# JFET.net
KiCad netlist of a schematic drawn in Altium Designer
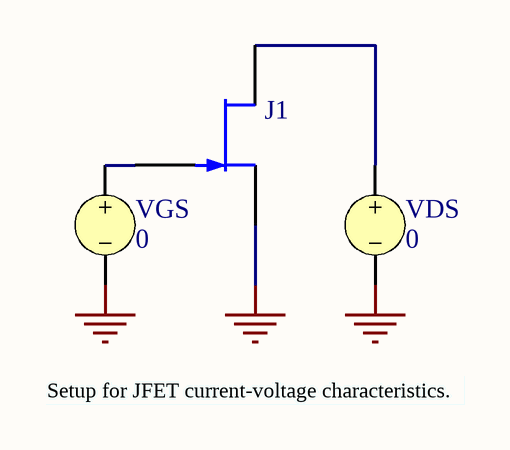
[diagram p0: JFET.SchDoc]

(export (version "E")
  (design (tool "Eeschema 10.0.6"))
  (components
    (comp (ref "J1")
      (value "NE38018-T1")
      (footprint "SOT343/P1.3")
      (description "N-channel junction fet")
      (libsource (lib "NE38018") (part "NE38018-T1"))
    )
    (comp (ref "VDS")
      (value "0")
      (description "Voltage Source")
      (fields (field (name "MANUFACTURER") "Generic Components") (field (name "Comment") "VSRC"))
      (libsource (lib "Simulation Sources") (part "VSRC"))
    )
    (comp (ref "VGS")
      (value "0")
      (description "Voltage Source")
      (fields (field (name "MANUFACTURER") "Generic Components") (field (name "Comment") "VSRC"))
      (libsource (lib "Simulation Sources") (part "VSRC"))
    )
  )
  (nets
    (net (code "1") (name "GND") (class "Default")
      (node (ref "J1") (pin "1") (pinfunction "S_1") (pintype "passive"))
      (node (ref "VDS") (pin "2") (pinfunction "2_2") (pintype "passive"))
      (node (ref "VGS") (pin "2") (pinfunction "2_2") (pintype "passive"))
    )
    (net (code "2") (name "Net-(J1-D)") (class "Default")
      (node (ref "J1") (pin "4") (pinfunction "D_4") (pintype "passive"))
      (node (ref "VDS") (pin "1") (pinfunction "1_1") (pintype "passive"))
    )
    (net (code "3") (name "Net-(J1-G)") (class "Default")
      (node (ref "J1") (pin "2") (pinfunction "G_2") (pintype "passive"))
      (node (ref "VGS") (pin "1") (pinfunction "1_1") (pintype "passive"))
    )
  )
)
